# TempControl.net
KiCad netlist of a schematic drawn in EAGLE
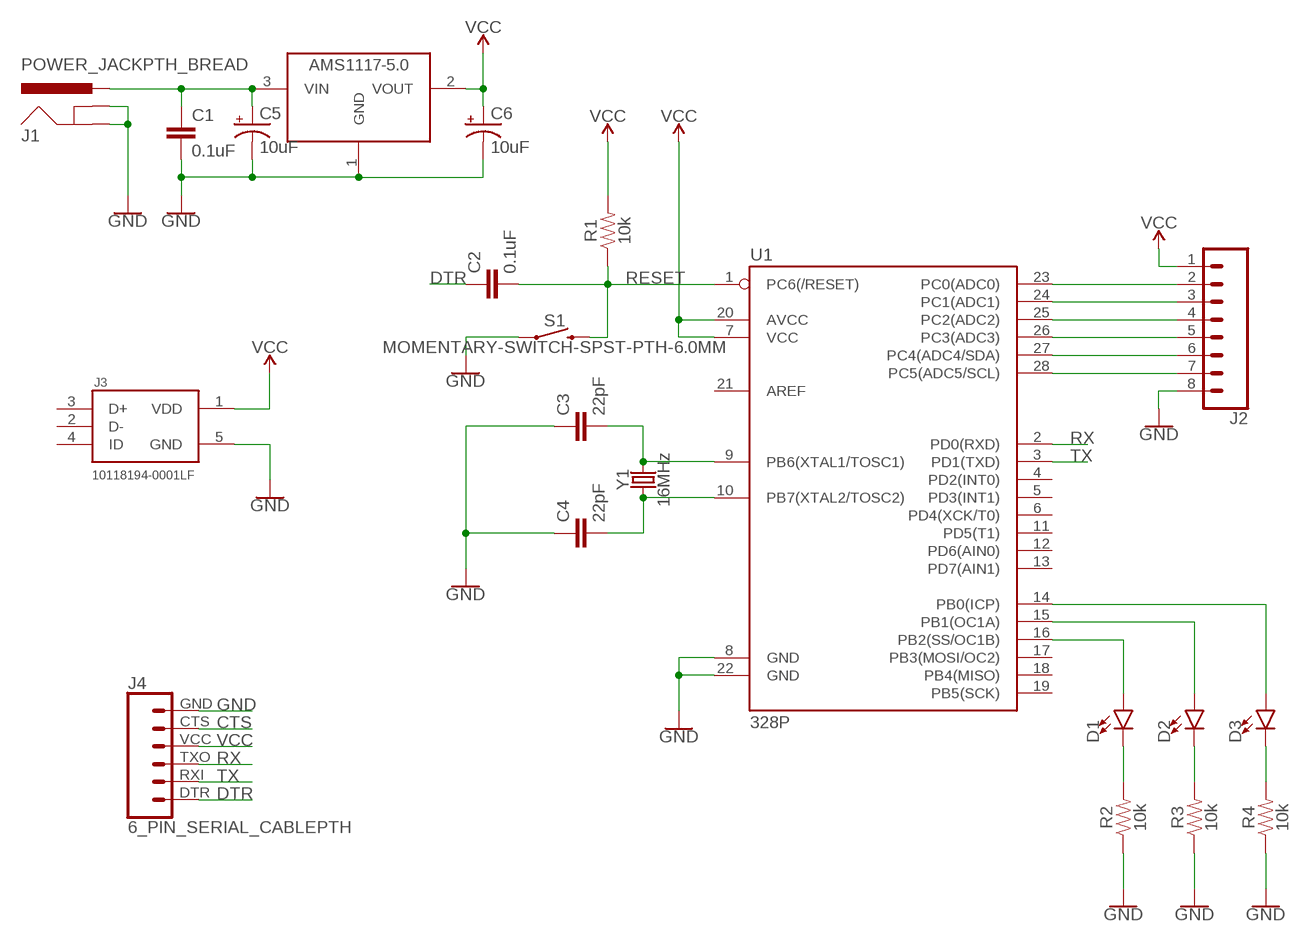
[diagram p0: schematic, sheet 1]

(export (version "E")
  (design (tool "Eeschema 10.0.6"))
  (components
    (comp (ref "C1")
      (value "0.1uF")
      (footprint "eagle-import:CAP-PTH-SMALL-KIT")
      (libsource (lib "eagle-import") (part "0.1UF-KIT-EZ-50V-20%"))
    )
    (comp (ref "C2")
      (value "0.1uF")
      (footprint "eagle-import:CAP-PTH-SMALL-KIT")
      (libsource (lib "eagle-import") (part "0.1UF-KIT-EZ-50V-20%"))
    )
    (comp (ref "C3")
      (value "22pF")
      (footprint "eagle-import:CAP-PTH-2.54")
      (libsource (lib "eagle-import") (part "22PF-PTH-2.54MM-200V-5%"))
    )
    (comp (ref "C4")
      (value "22pF")
      (footprint "eagle-import:CAP-PTH-2.54")
      (libsource (lib "eagle-import") (part "22PF-PTH-2.54MM-200V-5%"))
    )
    (comp (ref "C5")
      (value "10uF")
      (footprint "eagle-import:CPOL-RADIAL-2.5MM-5MM")
      (libsource (lib "eagle-import") (part "10UF-POLAR-RADIAL-2.5MM-25V-20%"))
    )
    (comp (ref "C6")
      (value "10uF")
      (footprint "eagle-import:CPOL-RADIAL-2.5MM-5MM")
      (libsource (lib "eagle-import") (part "10UF-POLAR-RADIAL-2.5MM-25V-20%"))
    )
    (comp (ref "D1")
      (value "LED5MM")
      (footprint "eagle-import:LED_5MM")
      (libsource (lib "eagle-import") (part "LED5MM"))
    )
    (comp (ref "D2")
      (value "LED5MM")
      (footprint "eagle-import:LED_5MM")
      (libsource (lib "eagle-import") (part "LED5MM"))
    )
    (comp (ref "D3")
      (value "LED5MM")
      (footprint "eagle-import:LED_5MM")
      (libsource (lib "eagle-import") (part "LED5MM"))
    )
    (comp (ref "J1")
      (value "POWER_JACKPTH_BREAD")
      (footprint "eagle-import:POWER_JACK_PTH_BREAD")
      (libsource (lib "eagle-import") (part "POWER_JACKPTH_BREAD"))
    )
    (comp (ref "J2")
      (value "CONN_08\"")
      (footprint "eagle-import:1X08")
      (libsource (lib "eagle-import") (part "CONN_08{dblquote}"))
    )
    (comp (ref "J3")
      (value "10118194-0001LF")
      (footprint "eagle-import:FRAMATOME_10118194-0001LF")
      (fields (field (name "MF") "Amphenol"))
      (libsource (lib "eagle-import") (part "10118194-0001LF"))
    )
    (comp (ref "J4")
      (value "6_PIN_SERIAL_CABLEPTH")
      (footprint "eagle-import:FTDI_BASIC")
      (libsource (lib "eagle-import") (part "6_PIN_SERIAL_CABLEPTH"))
    )
    (comp (ref "R1")
      (value "10k")
      (footprint "eagle-import:AXIAL-0.3")
      (libsource (lib "eagle-import") (part "10KOHM-HORIZ-1/4W-1%"))
    )
    (comp (ref "R2")
      (value "10k")
      (footprint "eagle-import:AXIAL-0.3")
      (libsource (lib "eagle-import") (part "10KOHM-HORIZ-1/4W-1%"))
    )
    (comp (ref "R3")
      (value "10k")
      (footprint "eagle-import:AXIAL-0.3")
      (libsource (lib "eagle-import") (part "10KOHM-HORIZ-1/4W-1%"))
    )
    (comp (ref "R4")
      (value "10k")
      (footprint "eagle-import:AXIAL-0.3")
      (libsource (lib "eagle-import") (part "10KOHM-HORIZ-1/4W-1%"))
    )
    (comp (ref "S1")
      (value "MOMENTARY-SWITCH-SPST-PTH-6.0MM")
      (footprint "eagle-import:TACTILE_SWITCH_PTH_6.0MM")
      (libsource (lib "eagle-import") (part "MOMENTARY-SWITCH-SPST-PTH-6.0MM"))
    )
    (comp (ref "U$1")
      (value "AMS1117-5.0")
      (footprint "eagle-import:SOT223")
      (fields (field (name "MF") "ams"))
      (libsource (lib "eagle-import") (part "AMS1117-5.0"))
    )
    (comp (ref "U1")
      (value "328P")
      (footprint "eagle-import:DIP28")
      (libsource (lib "eagle-import") (part "ATMEGA328P_PDIP"))
    )
    (comp (ref "Y1")
      (value "16MHz")
      (footprint "eagle-import:HC49US")
      (libsource (lib "eagle-import") (part "CRYSTAL-16MHZPTH-HC49US"))
    )
  )
  (nets
    (net (code "1") (name "/CTS") (class "Default")
      (node (ref "J4") (pin "CTS") (pinfunction "5_CTS") (pintype "passive"))
    )
    (net (code "2") (name "/DTR") (class "Default")
      (node (ref "C2") (pin "1") (pinfunction "1_1") (pintype "passive"))
      (node (ref "J4") (pin "DTR") (pinfunction "1_DTR") (pintype "passive"))
    )
    (net (code "3") (name "/RESET") (class "Default")
      (node (ref "C2") (pin "2") (pinfunction "2_2") (pintype "passive"))
      (node (ref "R1") (pin "P$1") (pinfunction "1_P$1") (pintype "passive"))
      (node (ref "S1") (pin "3") (pinfunction "2_3") (pintype "passive"))
      (node (ref "U1") (pin "1") (pinfunction "PC6(/RESET)_1") (pintype "bidirectional"))
    )
    (net (code "4") (name "/RX") (class "Default")
      (node (ref "J4") (pin "TXO") (pinfunction "3_TXO") (pintype "passive"))
      (node (ref "U1") (pin "2") (pinfunction "PD0(RXD)_2") (pintype "bidirectional"))
    )
    (net (code "5") (name "/TX") (class "Default")
      (node (ref "J4") (pin "RXI") (pinfunction "2_RXI") (pintype "passive"))
      (node (ref "U1") (pin "3") (pinfunction "PD1(TXD)_3") (pintype "bidirectional"))
    )
    (net (code "6") (name "GND") (class "Default")
      (node (ref "C1") (pin "2") (pinfunction "2_2") (pintype "passive"))
      (node (ref "C3") (pin "1") (pinfunction "1_1") (pintype "passive"))
      (node (ref "C4") (pin "1") (pinfunction "1_1") (pintype "passive"))
      (node (ref "C5") (pin "2") (pinfunction "-_2") (pintype "passive"))
      (node (ref "C6") (pin "2") (pinfunction "-_2") (pintype "passive"))
      (node (ref "J1") (pin "GND") (pinfunction "GND_GND") (pintype "bidirectional"))
      (node (ref "J1") (pin "GNDBREAK") (pinfunction "GNDBREAK_GNDBREAK") (pintype "bidirectional"))
      (node (ref "J2") (pin "8") (pinfunction "8_8") (pintype "passive"))
      (node (ref "J3") (pin "5") (pinfunction "GND_5") (pintype "power_in"))
      (node (ref "J4") (pin "GND") (pinfunction "6_GND") (pintype "passive"))
      (node (ref "R2") (pin "P$1") (pinfunction "1_P$1") (pintype "passive"))
      (node (ref "R3") (pin "P$1") (pinfunction "1_P$1") (pintype "passive"))
      (node (ref "R4") (pin "P$1") (pinfunction "1_P$1") (pintype "passive"))
      (node (ref "S1") (pin "1") (pinfunction "1_1") (pintype "passive"))
      (node (ref "U$1") (pin "1") (pinfunction "GND_1") (pintype "bidirectional"))
      (node (ref "U1") (pin "22") (pinfunction "GND_22") (pintype "bidirectional"))
      (node (ref "U1") (pin "8") (pinfunction "GND_8") (pintype "bidirectional"))
    )
    (net (code "7") (name "Net-(C5-+)") (class "Default")
      (node (ref "C1") (pin "1") (pinfunction "1_1") (pintype "passive"))
      (node (ref "C5") (pin "1") (pinfunction "+_1") (pintype "passive"))
      (node (ref "J1") (pin "PWR") (pinfunction "PWR_PWR") (pintype "bidirectional"))
      (node (ref "U$1") (pin "3") (pinfunction "VIN_3") (pintype "bidirectional"))
    )
    (net (code "8") (name "Net-(D1-C)") (class "Default")
      (node (ref "D1") (pin "K") (pinfunction "C_K") (pintype "passive"))
      (node (ref "R2") (pin "P$2") (pinfunction "2_P$2") (pintype "passive"))
    )
    (net (code "9") (name "Net-(D2-C)") (class "Default")
      (node (ref "D2") (pin "K") (pinfunction "C_K") (pintype "passive"))
      (node (ref "R3") (pin "P$2") (pinfunction "2_P$2") (pintype "passive"))
    )
    (net (code "10") (name "Net-(D3-C)") (class "Default")
      (node (ref "D3") (pin "K") (pinfunction "C_K") (pintype "passive"))
      (node (ref "R4") (pin "P$2") (pinfunction "2_P$2") (pintype "passive"))
    )
    (net (code "11") (name "Net-(U1-PB0(ICP))") (class "Default")
      (node (ref "D3") (pin "A") (pinfunction "A_A") (pintype "passive"))
      (node (ref "U1") (pin "14") (pinfunction "PB0(ICP)_14") (pintype "bidirectional"))
    )
    (net (code "12") (name "Net-(U1-PB1(OC1A))") (class "Default")
      (node (ref "D2") (pin "A") (pinfunction "A_A") (pintype "passive"))
      (node (ref "U1") (pin "15") (pinfunction "PB1(OC1A)_15") (pintype "bidirectional"))
    )
    (net (code "13") (name "Net-(U1-PB2(SS{slash}OC1B))") (class "Default")
      (node (ref "D1") (pin "A") (pinfunction "A_A") (pintype "passive"))
      (node (ref "U1") (pin "16") (pinfunction "PB2(SS/OC1B)_16") (pintype "bidirectional"))
    )
    (net (code "14") (name "Net-(U1-PB6(XTAL1{slash}TOSC1))") (class "Default")
      (node (ref "C3") (pin "2") (pinfunction "2_2") (pintype "passive"))
      (node (ref "U1") (pin "9") (pinfunction "PB6(XTAL1/TOSC1)_9") (pintype "bidirectional"))
      (node (ref "Y1") (pin "2") (pinfunction "2_2") (pintype "passive"))
    )
    (net (code "15") (name "Net-(U1-PB7(XTAL2{slash}TOSC2))") (class "Default")
      (node (ref "C4") (pin "2") (pinfunction "2_2") (pintype "passive"))
      (node (ref "U1") (pin "10") (pinfunction "PB7(XTAL2/TOSC2)_10") (pintype "bidirectional"))
      (node (ref "Y1") (pin "1") (pinfunction "1_1") (pintype "passive"))
    )
    (net (code "16") (name "Net-(U1-PC0(ADC0))") (class "Default")
      (node (ref "J2") (pin "2") (pinfunction "2_2") (pintype "passive"))
      (node (ref "U1") (pin "23") (pinfunction "PC0(ADC0)_23") (pintype "bidirectional"))
    )
    (net (code "17") (name "Net-(U1-PC1(ADC1))") (class "Default")
      (node (ref "J2") (pin "3") (pinfunction "3_3") (pintype "passive"))
      (node (ref "U1") (pin "24") (pinfunction "PC1(ADC1)_24") (pintype "bidirectional"))
    )
    (net (code "18") (name "Net-(U1-PC2(ADC2))") (class "Default")
      (node (ref "J2") (pin "4") (pinfunction "4_4") (pintype "passive"))
      (node (ref "U1") (pin "25") (pinfunction "PC2(ADC2)_25") (pintype "bidirectional"))
    )
    (net (code "19") (name "Net-(U1-PC3(ADC3))") (class "Default")
      (node (ref "J2") (pin "5") (pinfunction "5_5") (pintype "passive"))
      (node (ref "U1") (pin "26") (pinfunction "PC3(ADC3)_26") (pintype "bidirectional"))
    )
    (net (code "20") (name "Net-(U1-PC4(ADC4{slash}SDA))") (class "Default")
      (node (ref "J2") (pin "6") (pinfunction "6_6") (pintype "passive"))
      (node (ref "U1") (pin "27") (pinfunction "PC4(ADC4/SDA)_27") (pintype "bidirectional"))
    )
    (net (code "21") (name "Net-(U1-PC5(ADC5{slash}SCL))") (class "Default")
      (node (ref "J2") (pin "7") (pinfunction "7_7") (pintype "passive"))
      (node (ref "U1") (pin "28") (pinfunction "PC5(ADC5/SCL)_28") (pintype "bidirectional"))
    )
    (net (code "22") (name "VCC") (class "Default")
      (node (ref "C6") (pin "1") (pinfunction "+_1") (pintype "passive"))
      (node (ref "J2") (pin "1") (pinfunction "1_1") (pintype "passive"))
      (node (ref "J3") (pin "1") (pinfunction "VDD_1") (pintype "power_in"))
      (node (ref "J4") (pin "VCC") (pinfunction "4_VCC") (pintype "passive"))
      (node (ref "R1") (pin "P$2") (pinfunction "2_P$2") (pintype "passive"))
      (node (ref "U$1") (pin "2") (pinfunction "VOUT_2") (pintype "bidirectional"))
      (node (ref "U1") (pin "20") (pinfunction "AVCC_20") (pintype "bidirectional"))
      (node (ref "U1") (pin "7") (pinfunction "VCC_7") (pintype "bidirectional"))
    )
    (net (code "23") (name "unconnected-(J3-D+-Pad3)") (class "Default")
      (node (ref "J3") (pin "3") (pinfunction "D+_3") (pintype "bidirectional"))
    )
    (net (code "24") (name "unconnected-(J3-D--Pad2)") (class "Default")
      (node (ref "J3") (pin "2") (pinfunction "D-_2") (pintype "bidirectional"))
    )
    (net (code "25") (name "unconnected-(J3-ID-Pad4)") (class "Default")
      (node (ref "J3") (pin "4") (pinfunction "ID_4") (pintype "passive"))
    )
    (net (code "26") (name "unconnected-(U1-AREF-Pad21)") (class "Default")
      (node (ref "U1") (pin "21") (pinfunction "AREF_21") (pintype "bidirectional"))
    )
    (net (code "27") (name "unconnected-(U1-PB3(MOSI{slash}OC2)-Pad17)") (class "Default")
      (node (ref "U1") (pin "17") (pinfunction "PB3(MOSI/OC2)_17") (pintype "bidirectional"))
    )
    (net (code "28") (name "unconnected-(U1-PB4(MISO)-Pad18)") (class "Default")
      (node (ref "U1") (pin "18") (pinfunction "PB4(MISO)_18") (pintype "bidirectional"))
    )
    (net (code "29") (name "unconnected-(U1-PB5(SCK)-Pad19)") (class "Default")
      (node (ref "U1") (pin "19") (pinfunction "PB5(SCK)_19") (pintype "bidirectional"))
    )
    (net (code "30") (name "unconnected-(U1-PD2(INT0)-Pad4)") (class "Default")
      (node (ref "U1") (pin "4") (pinfunction "PD2(INT0)_4") (pintype "bidirectional"))
    )
    (net (code "31") (name "unconnected-(U1-PD3(INT1)-Pad5)") (class "Default")
      (node (ref "U1") (pin "5") (pinfunction "PD3(INT1)_5") (pintype "bidirectional"))
    )
    (net (code "32") (name "unconnected-(U1-PD4(XCK{slash}T0)-Pad6)") (class "Default")
      (node (ref "U1") (pin "6") (pinfunction "PD4(XCK/T0)_6") (pintype "bidirectional"))
    )
    (net (code "33") (name "unconnected-(U1-PD5(T1)-Pad11)") (class "Default")
      (node (ref "U1") (pin "11") (pinfunction "PD5(T1)_11") (pintype "bidirectional"))
    )
    (net (code "34") (name "unconnected-(U1-PD6(AIN0)-Pad12)") (class "Default")
      (node (ref "U1") (pin "12") (pinfunction "PD6(AIN0)_12") (pintype "bidirectional"))
    )
    (net (code "35") (name "unconnected-(U1-PD7(AIN1)-Pad13)") (class "Default")
      (node (ref "U1") (pin "13") (pinfunction "PD7(AIN1)_13") (pintype "bidirectional"))
    )
  )
)
